# MIET_464512_002_E3_Sheet_2.net
KiCad netlist of a schematic drawn in Altium Designer
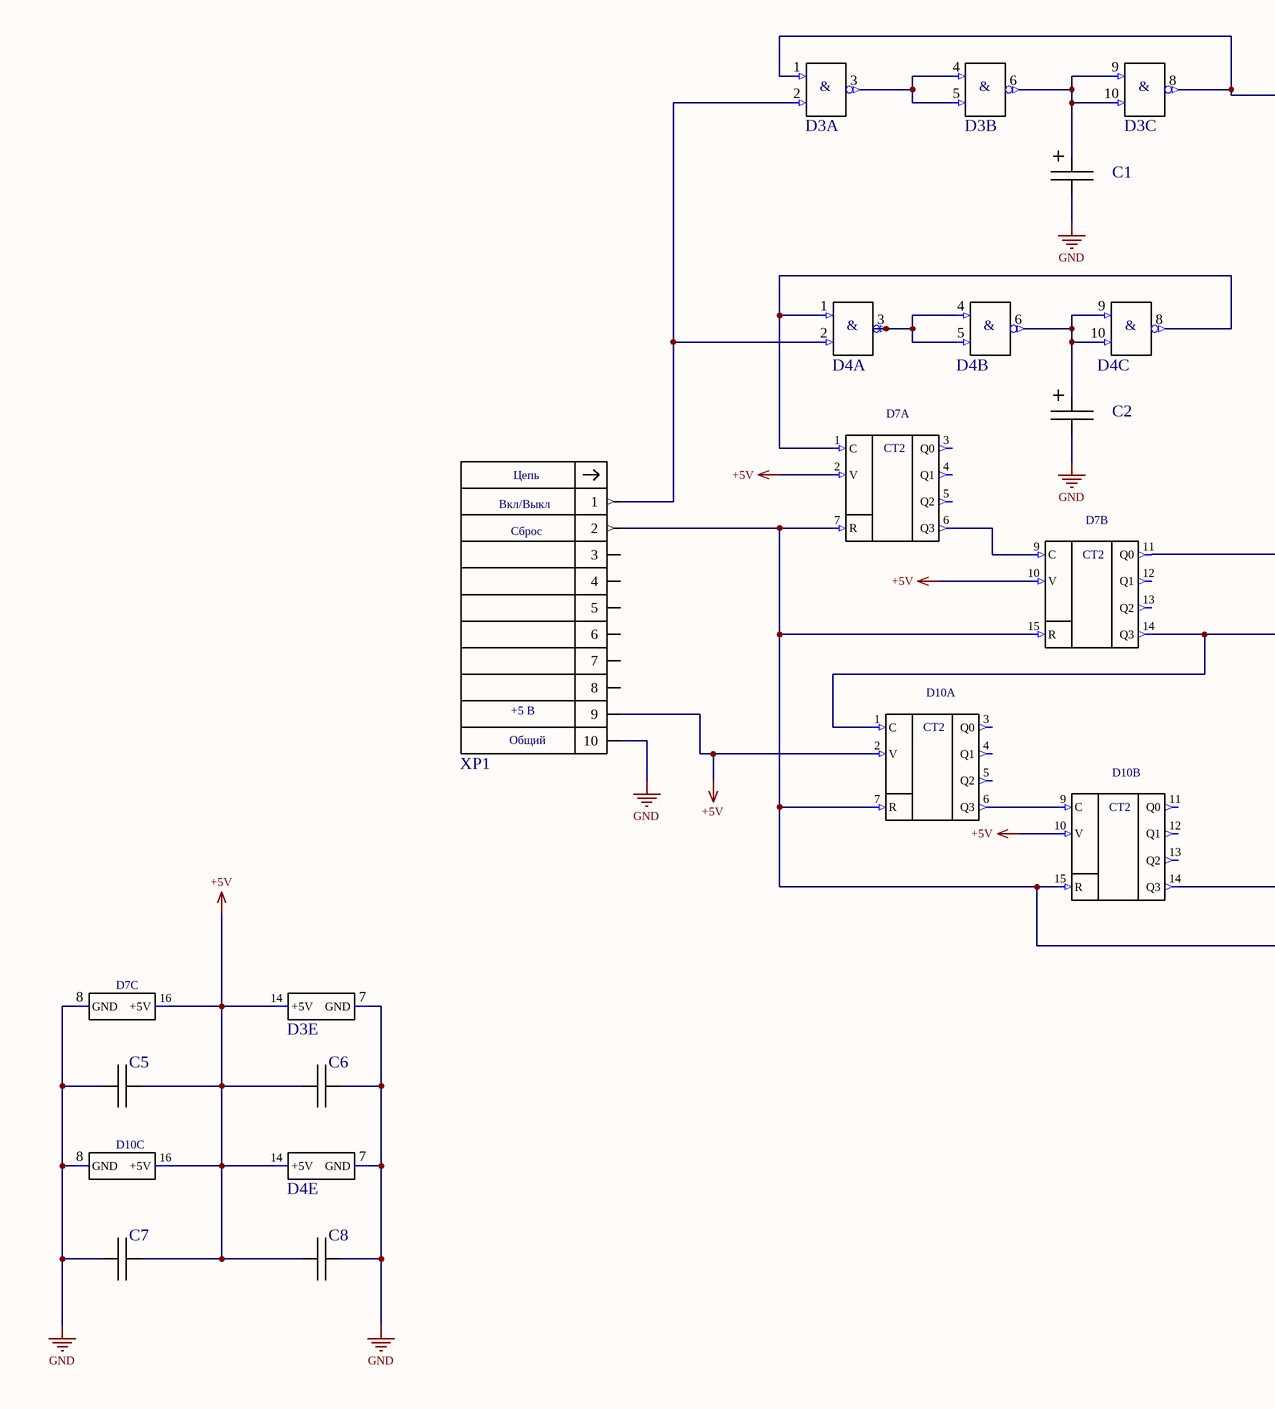
[diagram p0: MIET_464512_002_E3_Sheet_2.SchDoc, left]
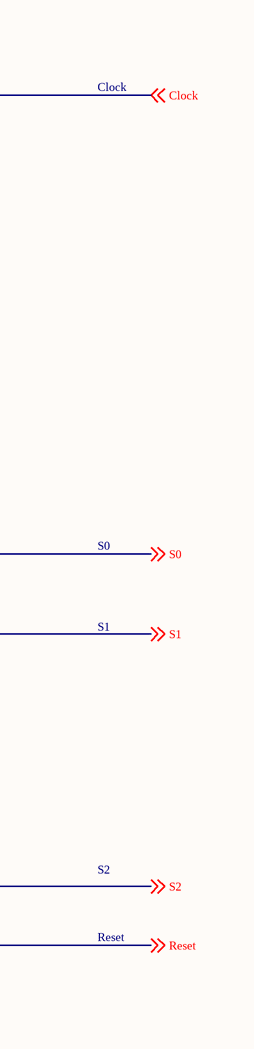
[diagram p1: MIET_464512_002_E3_Sheet_2.SchDoc, right]

(export (version "E")
  (design (tool "Eeschema 10.0.6"))
  (components
    (comp (ref "C1")
      (value "C")
      (footprint "C-Tantal")
      (description "К53-65 Конденсатор танталовый C(6032) 0,47-100 мкФ")
      (fields
        (field (name "MANUFACTURER") "ОАО \"Элеконд\"")
        (field (name "TOLERANCE") "10%")
        (field (name "CREATED_BY") "Желобаев")
      )
      (libsource (lib "Int_Library_for_Lessons") (part "K53-65_C_10%"))
    )
    (comp (ref "C2")
      (value "C")
      (footprint "C-Tantal")
      (description "К53-65 Конденсатор танталовый C(6032) 0,47-100 мкФ")
      (fields
        (field (name "MANUFACTURER") "ОАО \"Элеконд\"")
        (field (name "TOLERANCE") "10%")
        (field (name "CREATED_BY") "Желобаев")
      )
      (libsource (lib "Int_Library_for_Lessons") (part "K53-65_C_10%"))
    )
    (comp (ref "C5")
      (value "~")
      (footprint "0805_N")
      (description "Чип конденсатор 0805 Н90 ряд Е6")
      (fields
        (field (name "MANUFACTURER") "ООО \"Кулон\"")
        (field (name "TOLERANCE") "+80%-20%")
        (field (name "CREATED_BY") "Желобаев")
      )
      (libsource (lib "Int_Library_for_Lessons") (part "К10-79_0805_Н90"))
    )
    (comp (ref "C6")
      (value "~")
      (footprint "0805_N")
      (description "Чип конденсатор 0805 Н90 ряд Е6")
      (fields
        (field (name "MANUFACTURER") "ООО \"Кулон\"")
        (field (name "TOLERANCE") "+80%-20%")
        (field (name "CREATED_BY") "Желобаев")
      )
      (libsource (lib "Int_Library_for_Lessons") (part "К10-79_0805_Н90"))
    )
    (comp (ref "C7")
      (value "~")
      (footprint "0805_N")
      (description "Чип конденсатор 0805 Н90 ряд Е6")
      (fields
        (field (name "MANUFACTURER") "ООО \"Кулон\"")
        (field (name "TOLERANCE") "+80%-20%")
        (field (name "CREATED_BY") "Желобаев")
      )
      (libsource (lib "Int_Library_for_Lessons") (part "К10-79_0805_Н90"))
    )
    (comp (ref "C8")
      (value "~")
      (footprint "0805_N")
      (description "Чип конденсатор 0805 Н90 ряд Е6")
      (fields
        (field (name "MANUFACTURER") "ООО \"Кулон\"")
        (field (name "TOLERANCE") "+80%-20%")
        (field (name "CREATED_BY") "Желобаев")
      )
      (libsource (lib "Int_Library_for_Lessons") (part "К10-79_0805_Н90"))
    )
    (comp (ref "D3")
      (value "74AC00PC")
      (footprint "DIP14")
      (description "4 элемента 2И-НЕ TTL PDIP-14")
      (fields (field (name "MANUFACTURER") "ON Semiconductor") (field (name "CREATED_BY") "Желобаев"))
      (libsource (lib "Int_Library_for_Lessons") (part "74AC00PC"))
    )
    (comp (ref "D4")
      (value "74AC00PC")
      (footprint "DIP14")
      (description "4 элемента 2И-НЕ TTL PDIP-14")
      (fields (field (name "MANUFACTURER") "ON Semiconductor") (field (name "CREATED_BY") "Желобаев"))
      (libsource (lib "Int_Library_for_Lessons") (part "74AC00PC"))
    )
    (comp (ref "D7")
      (value "MC14520BCP")
      (footprint "DIP16")
      (description "Два двоичных счетчика")
      (fields (field (name "MANUFACTURER") "Motorola") (field (name "CREATED_BY") "Желобаев"))
      (libsource (lib "Int_Library_for_Lessons") (part "MC14520BCP"))
    )
    (comp (ref "D10")
      (value "MC14520BCP")
      (footprint "DIP16")
      (description "Два двоичных счетчика")
      (fields (field (name "MANUFACTURER") "Motorola") (field (name "CREATED_BY") "Желобаев"))
      (libsource (lib "Int_Library_for_Lessons") (part "MC14520BCP"))
    )
    (comp (ref "XP1")
      (value "TE_1-1634689-0")
      (footprint "BH-10R")
      (description "Вилка типа BH-10R угловая правая двухрядная 2х5х2.54")
      (fields (field (name "MANUFACTURER") "TE Connectivity") (field (name "CREATED_BY") "Желобаев"))
      (libsource (lib "Int_Library_for_Lessons") (part "TE_1-1634689-0"))
    )
  )
  (nets
    (net (code "1") (name "+5V") (class "Default")
      (node (ref "C5") (pin "2") (pinfunction "2_2") (pintype "passive"))
      (node (ref "C6") (pin "1") (pinfunction "1_1") (pintype "passive"))
      (node (ref "C7") (pin "2") (pinfunction "2_2") (pintype "passive"))
      (node (ref "C8") (pin "1") (pinfunction "1_1") (pintype "passive"))
      (node (ref "D10") (pin "10") (pinfunction "V_10") (pintype "input"))
      (node (ref "D10") (pin "16") (pinfunction "+5V_16") (pintype "power_in"))
      (node (ref "D10") (pin "2") (pinfunction "V_2") (pintype "input"))
      (node (ref "D3") (pin "14") (pinfunction "+5V_14") (pintype "power_in"))
      (node (ref "D4") (pin "14") (pinfunction "+5V_14") (pintype "power_in"))
      (node (ref "D7") (pin "10") (pinfunction "V_10") (pintype "input"))
      (node (ref "D7") (pin "16") (pinfunction "+5V_16") (pintype "power_in"))
      (node (ref "D7") (pin "2") (pinfunction "V_2") (pintype "input"))
      (node (ref "XP1") (pin "9") (pinfunction "9_9") (pintype "power_in"))
    )
    (net (code "2") (name "Clock") (class "Default")
      (node (ref "D3") (pin "1") (pinfunction "In1_1") (pintype "input"))
      (node (ref "D3") (pin "8") (pinfunction "Out_8") (pintype "output"))
    )
    (net (code "3") (name "GND") (class "Default")
      (node (ref "C1") (pin "-") (pinfunction "-_-") (pintype "passive"))
      (node (ref "C2") (pin "-") (pinfunction "-_-") (pintype "passive"))
      (node (ref "C5") (pin "1") (pinfunction "1_1") (pintype "passive"))
      (node (ref "C6") (pin "2") (pinfunction "2_2") (pintype "passive"))
      (node (ref "C7") (pin "1") (pinfunction "1_1") (pintype "passive"))
      (node (ref "C8") (pin "2") (pinfunction "2_2") (pintype "passive"))
      (node (ref "D10") (pin "8") (pinfunction "GND_8") (pintype "power_in"))
      (node (ref "D3") (pin "7") (pinfunction "GND_7") (pintype "power_in"))
      (node (ref "D4") (pin "7") (pinfunction "GND_7") (pintype "power_in"))
      (node (ref "D7") (pin "8") (pinfunction "GND_8") (pintype "power_in"))
      (node (ref "XP1") (pin "10") (pinfunction "10_10") (pintype "power_in"))
    )
    (net (code "4") (name "Net-(D3A-In2)") (class "Default")
      (node (ref "D3") (pin "2") (pinfunction "In2_2") (pintype "input"))
      (node (ref "D4") (pin "2") (pinfunction "In2_2") (pintype "input"))
      (node (ref "XP1") (pin "1") (pinfunction "1_1") (pintype "output"))
    )
    (net (code "5") (name "Net-(D3A-Out)") (class "Default")
      (node (ref "D3") (pin "3") (pinfunction "Out_3") (pintype "output"))
      (node (ref "D3") (pin "4") (pinfunction "In1_4") (pintype "input"))
      (node (ref "D3") (pin "5") (pinfunction "In2_5") (pintype "input"))
    )
    (net (code "6") (name "Net-(D3B-Out)") (class "Default")
      (node (ref "C1") (pin "+") (pinfunction "+_+") (pintype "passive"))
      (node (ref "D3") (pin "10") (pinfunction "In2_10") (pintype "input"))
      (node (ref "D3") (pin "6") (pinfunction "Out_6") (pintype "output"))
      (node (ref "D3") (pin "9") (pinfunction "In1_9") (pintype "input"))
    )
    (net (code "7") (name "Net-(D4A-In1)") (class "Default")
      (node (ref "D4") (pin "1") (pinfunction "In1_1") (pintype "input"))
      (node (ref "D4") (pin "8") (pinfunction "Out_8") (pintype "output"))
      (node (ref "D7") (pin "1") (pinfunction "C_1") (pintype "input"))
    )
    (net (code "8") (name "Net-(D4A-Out)") (class "Default")
      (node (ref "D4") (pin "3") (pinfunction "Out_3") (pintype "output"))
      (node (ref "D4") (pin "4") (pinfunction "In1_4") (pintype "input"))
      (node (ref "D4") (pin "5") (pinfunction "In2_5") (pintype "input"))
    )
    (net (code "9") (name "Net-(D4B-Out)") (class "Default")
      (node (ref "C2") (pin "+") (pinfunction "+_+") (pintype "passive"))
      (node (ref "D4") (pin "10") (pinfunction "In2_10") (pintype "input"))
      (node (ref "D4") (pin "6") (pinfunction "Out_6") (pintype "output"))
      (node (ref "D4") (pin "9") (pinfunction "In1_9") (pintype "input"))
    )
    (net (code "10") (name "Net-(D7A-Q3)") (class "Default")
      (node (ref "D7") (pin "6") (pinfunction "Q3_6") (pintype "output"))
      (node (ref "D7") (pin "9") (pinfunction "C_9") (pintype "input"))
    )
    (net (code "11") (name "Net-(D10A-Q3)") (class "Default")
      (node (ref "D10") (pin "6") (pinfunction "Q3_6") (pintype "output"))
      (node (ref "D10") (pin "9") (pinfunction "C_9") (pintype "input"))
    )
    (net (code "12") (name "Reset") (class "Default")
      (node (ref "D10") (pin "15") (pinfunction "R_15") (pintype "input"))
      (node (ref "D10") (pin "7") (pinfunction "R_7") (pintype "input"))
      (node (ref "D7") (pin "15") (pinfunction "R_15") (pintype "input"))
      (node (ref "D7") (pin "7") (pinfunction "R_7") (pintype "input"))
      (node (ref "XP1") (pin "2") (pinfunction "2_2") (pintype "output"))
    )
    (net (code "13") (name "S0") (class "Default")
      (node (ref "D7") (pin "11") (pinfunction "Q0_11") (pintype "output"))
    )
    (net (code "14") (name "S1") (class "Default")
      (node (ref "D10") (pin "1") (pinfunction "C_1") (pintype "input"))
      (node (ref "D7") (pin "14") (pinfunction "Q3_14") (pintype "output"))
    )
    (net (code "15") (name "S2") (class "Default")
      (node (ref "D10") (pin "14") (pinfunction "Q3_14") (pintype "output"))
    )
    (net (code "16") (name "unconnected-(D7A-Q0-Pad3)") (class "Default")
      (node (ref "D7") (pin "3") (pinfunction "Q0_3") (pintype "output"))
    )
    (net (code "17") (name "unconnected-(D7A-Q1-Pad4)") (class "Default")
      (node (ref "D7") (pin "4") (pinfunction "Q1_4") (pintype "output"))
    )
    (net (code "18") (name "unconnected-(D7A-Q2-Pad5)") (class "Default")
      (node (ref "D7") (pin "5") (pinfunction "Q2_5") (pintype "output"))
    )
    (net (code "19") (name "unconnected-(D7B-Q1-Pad12)") (class "Default")
      (node (ref "D7") (pin "12") (pinfunction "Q1_12") (pintype "output"))
    )
    (net (code "20") (name "unconnected-(D7B-Q2-Pad13)") (class "Default")
      (node (ref "D7") (pin "13") (pinfunction "Q2_13") (pintype "output"))
    )
    (net (code "21") (name "unconnected-(D10A-Q0-Pad3)") (class "Default")
      (node (ref "D10") (pin "3") (pinfunction "Q0_3") (pintype "output"))
    )
    (net (code "22") (name "unconnected-(D10A-Q1-Pad4)") (class "Default")
      (node (ref "D10") (pin "4") (pinfunction "Q1_4") (pintype "output"))
    )
    (net (code "23") (name "unconnected-(D10A-Q2-Pad5)") (class "Default")
      (node (ref "D10") (pin "5") (pinfunction "Q2_5") (pintype "output"))
    )
    (net (code "24") (name "unconnected-(D10B-Q0-Pad11)") (class "Default")
      (node (ref "D10") (pin "11") (pinfunction "Q0_11") (pintype "output"))
    )
    (net (code "25") (name "unconnected-(D10B-Q1-Pad12)") (class "Default")
      (node (ref "D10") (pin "12") (pinfunction "Q1_12") (pintype "output"))
    )
    (net (code "26") (name "unconnected-(D10B-Q2-Pad13)") (class "Default")
      (node (ref "D10") (pin "13") (pinfunction "Q2_13") (pintype "output"))
    )
    (net (code "27") (name "unconnected-(XP1-Pad3)") (class "Default")
      (node (ref "XP1") (pin "3") (pinfunction "3_3") (pintype "passive"))
    )
    (net (code "28") (name "unconnected-(XP1-Pad4)") (class "Default")
      (node (ref "XP1") (pin "4") (pinfunction "4_4") (pintype "passive"))
    )
    (net (code "29") (name "unconnected-(XP1-Pad5)") (class "Default")
      (node (ref "XP1") (pin "5") (pinfunction "5_5") (pintype "passive"))
    )
    (net (code "30") (name "unconnected-(XP1-Pad6)") (class "Default")
      (node (ref "XP1") (pin "6") (pinfunction "6_6") (pintype "passive"))
    )
    (net (code "31") (name "unconnected-(XP1-Pad7)") (class "Default")
      (node (ref "XP1") (pin "7") (pinfunction "7_7") (pintype "passive"))
    )
    (net (code "32") (name "unconnected-(XP1-Pad8)") (class "Default")
      (node (ref "XP1") (pin "8") (pinfunction "8_8") (pintype "passive"))
    )
  )
)
